# tophat-alumni.net
KiCad netlist of a schematic drawn in EAGLE
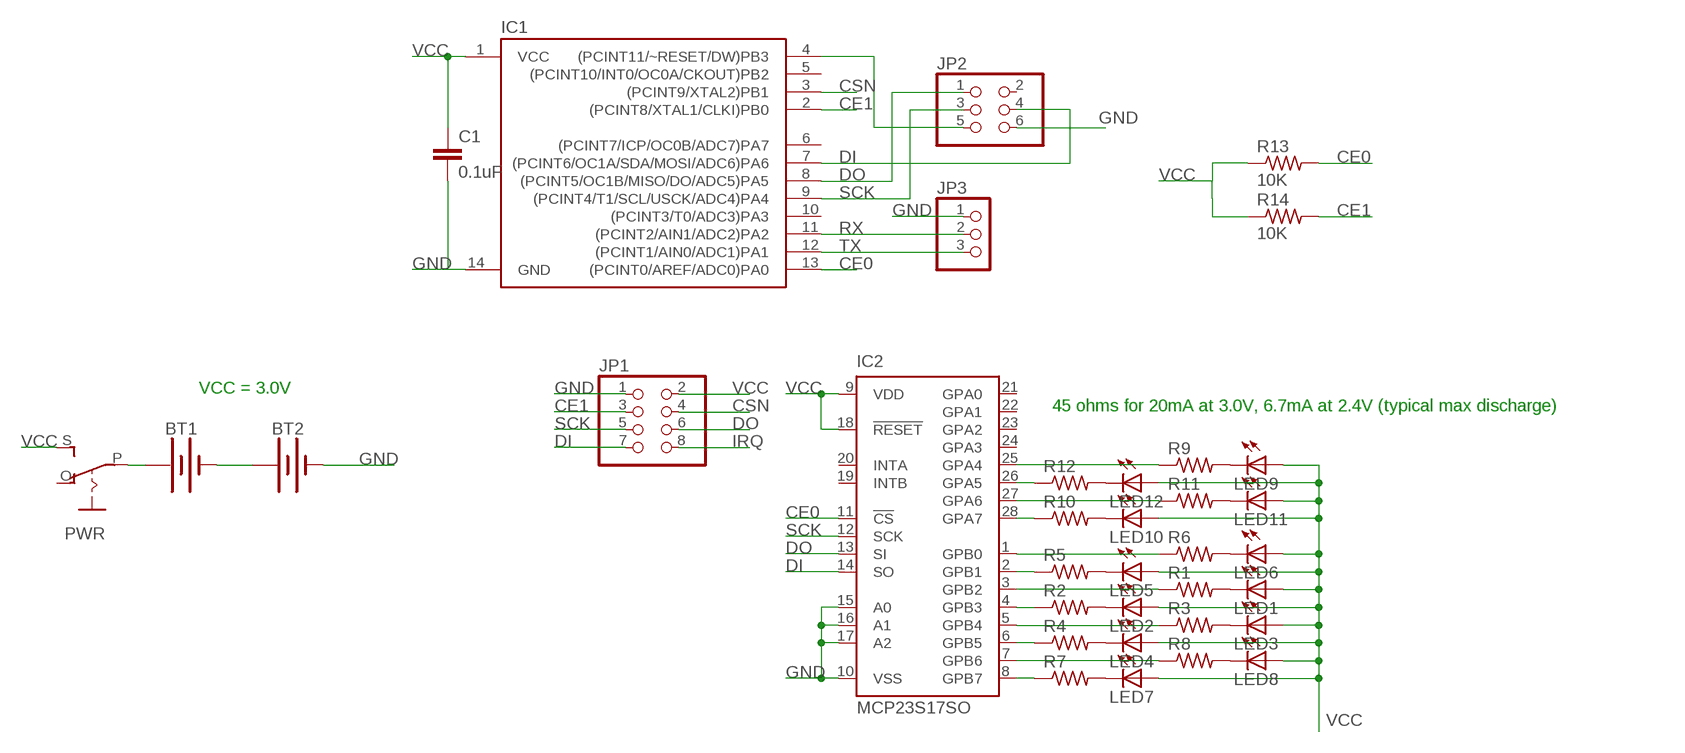
[diagram p0: schematic, sheet 1]

(export (version "E")
  (design (tool "Eeschema 10.0.6"))
  (components
    (comp (ref "BT1")
      (value "BATTERY-AA-SMD")
      (footprint "eagle-import:BATTERY-AA-SMD")
      (libsource (lib "eagle-import") (part "BATTERY-AA-SMD"))
    )
    (comp (ref "BT2")
      (value "BATTERY-AA-SMD")
      (footprint "eagle-import:BATTERY-AA-SMD")
      (libsource (lib "eagle-import") (part "BATTERY-AA-SMD"))
    )
    (comp (ref "C1")
      (value "0.1uF")
      (footprint "eagle-import:C1206")
      (libsource (lib "eagle-import") (part "C-EUC1206"))
    )
    (comp (ref "IC1")
      (value "ATTINY84")
      (footprint "eagle-import:SO14")
      (libsource (lib "eagle-import") (part "ATTINY84"))
    )
    (comp (ref "IC2")
      (value "MCP23S17SO")
      (footprint "eagle-import:SO28W")
      (fields (field (name "MF") "MICROCHIP") (field (name "MPN") "MCP23S17-E/SO"))
      (libsource (lib "eagle-import") (part "MCP23S17SO"))
    )
    (comp (ref "JP1")
      (value "PINHD-2X4/90")
      (footprint "eagle-import:2X04_90")
      (libsource (lib "eagle-import") (part "PINHD-2X4/90"))
    )
    (comp (ref "JP2")
      (value "PINHD-2X3")
      (footprint "eagle-import:2X03")
      (libsource (lib "eagle-import") (part "PINHD-2X3"))
    )
    (comp (ref "JP3")
      (value "PINHD-1X3")
      (footprint "eagle-import:1X03")
      (libsource (lib "eagle-import") (part "PINHD-1X3"))
    )
    (comp (ref "LED1")
      (value "LEDSMT1206")
      (footprint "eagle-import:1206")
      (libsource (lib "eagle-import") (part "LEDSMT1206"))
    )
    (comp (ref "LED2")
      (value "LEDSMT1206")
      (footprint "eagle-import:1206")
      (libsource (lib "eagle-import") (part "LEDSMT1206"))
    )
    (comp (ref "LED3")
      (value "LEDSMT1206")
      (footprint "eagle-import:1206")
      (libsource (lib "eagle-import") (part "LEDSMT1206"))
    )
    (comp (ref "LED4")
      (value "LEDSMT1206")
      (footprint "eagle-import:1206")
      (libsource (lib "eagle-import") (part "LEDSMT1206"))
    )
    (comp (ref "LED5")
      (value "LEDSMT1206")
      (footprint "eagle-import:1206")
      (libsource (lib "eagle-import") (part "LEDSMT1206"))
    )
    (comp (ref "LED6")
      (value "LEDSMT1206")
      (footprint "eagle-import:1206")
      (libsource (lib "eagle-import") (part "LEDSMT1206"))
    )
    (comp (ref "LED7")
      (value "LEDSMT1206")
      (footprint "eagle-import:1206")
      (libsource (lib "eagle-import") (part "LEDSMT1206"))
    )
    (comp (ref "LED8")
      (value "LEDSMT1206")
      (footprint "eagle-import:1206")
      (libsource (lib "eagle-import") (part "LEDSMT1206"))
    )
    (comp (ref "LED9")
      (value "LEDSMT1206")
      (footprint "eagle-import:1206")
      (libsource (lib "eagle-import") (part "LEDSMT1206"))
    )
    (comp (ref "LED10")
      (value "LEDSMT1206")
      (footprint "eagle-import:1206")
      (libsource (lib "eagle-import") (part "LEDSMT1206"))
    )
    (comp (ref "LED11")
      (value "LEDSMT1206")
      (footprint "eagle-import:1206")
      (libsource (lib "eagle-import") (part "LEDSMT1206"))
    )
    (comp (ref "LED12")
      (value "LEDSMT1206")
      (footprint "eagle-import:1206")
      (libsource (lib "eagle-import") (part "LEDSMT1206"))
    )
    (comp (ref "PWR")
      (value "EG1218S")
      (footprint "eagle-import:EG1218")
      (libsource (lib "eagle-import") (part "EG1218S"))
    )
    (comp (ref "R1")
      (value "R-US_R1206")
      (footprint "eagle-import:R1206")
      (libsource (lib "eagle-import") (part "R-US_R1206"))
    )
    (comp (ref "R2")
      (value "R-US_R1206")
      (footprint "eagle-import:R1206")
      (libsource (lib "eagle-import") (part "R-US_R1206"))
    )
    (comp (ref "R3")
      (value "R-US_R1206")
      (footprint "eagle-import:R1206")
      (libsource (lib "eagle-import") (part "R-US_R1206"))
    )
    (comp (ref "R4")
      (value "R-US_R1206")
      (footprint "eagle-import:R1206")
      (libsource (lib "eagle-import") (part "R-US_R1206"))
    )
    (comp (ref "R5")
      (value "R-US_R1206")
      (footprint "eagle-import:R1206")
      (libsource (lib "eagle-import") (part "R-US_R1206"))
    )
    (comp (ref "R6")
      (value "R-US_R1206")
      (footprint "eagle-import:R1206")
      (libsource (lib "eagle-import") (part "R-US_R1206"))
    )
    (comp (ref "R7")
      (value "R-US_R1206")
      (footprint "eagle-import:R1206")
      (libsource (lib "eagle-import") (part "R-US_R1206"))
    )
    (comp (ref "R8")
      (value "R-US_R1206")
      (footprint "eagle-import:R1206")
      (libsource (lib "eagle-import") (part "R-US_R1206"))
    )
    (comp (ref "R9")
      (value "R-US_R1206")
      (footprint "eagle-import:R1206")
      (libsource (lib "eagle-import") (part "R-US_R1206"))
    )
    (comp (ref "R10")
      (value "R-US_R1206")
      (footprint "eagle-import:R1206")
      (libsource (lib "eagle-import") (part "R-US_R1206"))
    )
    (comp (ref "R11")
      (value "R-US_R1206")
      (footprint "eagle-import:R1206")
      (libsource (lib "eagle-import") (part "R-US_R1206"))
    )
    (comp (ref "R12")
      (value "R-US_R1206")
      (footprint "eagle-import:R1206")
      (libsource (lib "eagle-import") (part "R-US_R1206"))
    )
    (comp (ref "R13")
      (value "10K")
      (footprint "eagle-import:R1206")
      (libsource (lib "eagle-import") (part "R-US_R1206"))
    )
    (comp (ref "R14")
      (value "10K")
      (footprint "eagle-import:R1206")
      (libsource (lib "eagle-import") (part "R-US_R1206"))
    )
  )
  (nets
    (net (code "1") (name "/CE0") (class "Default")
      (node (ref "IC1") (pin "13") (pinfunction "(PCINT0/AREF/ADC0)PA0_13") (pintype "bidirectional"))
      (node (ref "IC2") (pin "11") (pinfunction "~{CS}_11") (pintype "input"))
      (node (ref "R13") (pin "2") (pinfunction "2_2") (pintype "passive"))
    )
    (net (code "2") (name "/CE1") (class "Default")
      (node (ref "IC1") (pin "2") (pinfunction "(PCINT8/XTAL1/CLKI)PB0_2") (pintype "bidirectional"))
      (node (ref "JP1") (pin "3") (pinfunction "3_3") (pintype "passive"))
      (node (ref "R14") (pin "2") (pinfunction "2_2") (pintype "passive"))
    )
    (net (code "3") (name "/CSN") (class "Default")
      (node (ref "IC1") (pin "3") (pinfunction "(PCINT9/XTAL2)PB1_3") (pintype "bidirectional"))
      (node (ref "JP1") (pin "4") (pinfunction "4_4") (pintype "passive"))
    )
    (net (code "4") (name "/DI") (class "Default")
      (node (ref "IC1") (pin "7") (pinfunction "(PCINT6/OC1A/SDA/MOSI/ADC6)PA6_7") (pintype "bidirectional"))
      (node (ref "IC2") (pin "14") (pinfunction "SO_14") (pintype "output"))
      (node (ref "JP1") (pin "7") (pinfunction "7_7") (pintype "passive"))
      (node (ref "JP2") (pin "4") (pinfunction "4_4") (pintype "passive"))
    )
    (net (code "5") (name "/DO") (class "Default")
      (node (ref "IC1") (pin "8") (pinfunction "(PCINT5/OC1B/MISO/DO/ADC5)PA5_8") (pintype "bidirectional"))
      (node (ref "IC2") (pin "13") (pinfunction "SI_13") (pintype "input"))
      (node (ref "JP1") (pin "6") (pinfunction "6_6") (pintype "passive"))
      (node (ref "JP2") (pin "1") (pinfunction "1_1") (pintype "passive"))
    )
    (net (code "6") (name "/GND") (class "Default")
      (node (ref "BT2") (pin "P$2") (pinfunction "-_P$2") (pintype "power_in"))
      (node (ref "BT2") (pin "P$4") (pinfunction "-_P$4") (pintype "power_in"))
      (node (ref "C1") (pin "2") (pinfunction "2_2") (pintype "passive"))
      (node (ref "IC1") (pin "14") (pinfunction "GND_14") (pintype "bidirectional"))
      (node (ref "IC2") (pin "10") (pinfunction "VSS_10") (pintype "power_in"))
      (node (ref "IC2") (pin "15") (pinfunction "A0_15") (pintype "input"))
      (node (ref "IC2") (pin "16") (pinfunction "A1_16") (pintype "input"))
      (node (ref "IC2") (pin "17") (pinfunction "A2_17") (pintype "input"))
      (node (ref "JP1") (pin "1") (pinfunction "1_1") (pintype "passive"))
      (node (ref "JP2") (pin "6") (pinfunction "6_6") (pintype "passive"))
      (node (ref "JP3") (pin "1") (pinfunction "1_1") (pintype "passive"))
    )
    (net (code "7") (name "/IRQ") (class "Default")
      (node (ref "JP1") (pin "8") (pinfunction "8_8") (pintype "passive"))
    )
    (net (code "8") (name "/RX") (class "Default")
      (node (ref "IC1") (pin "11") (pinfunction "(PCINT2/AIN1/ADC2)PA2_11") (pintype "bidirectional"))
      (node (ref "JP3") (pin "2") (pinfunction "2_2") (pintype "passive"))
    )
    (net (code "9") (name "/SCK") (class "Default")
      (node (ref "IC1") (pin "9") (pinfunction "(PCINT4/T1/SCL/USCK/ADC4)PA4_9") (pintype "bidirectional"))
      (node (ref "IC2") (pin "12") (pinfunction "SCK_12") (pintype "input"))
      (node (ref "JP1") (pin "5") (pinfunction "5_5") (pintype "passive"))
      (node (ref "JP2") (pin "3") (pinfunction "3_3") (pintype "passive"))
    )
    (net (code "10") (name "/TX") (class "Default")
      (node (ref "IC1") (pin "12") (pinfunction "(PCINT1/AIN0/ADC1)PA1_12") (pintype "bidirectional"))
      (node (ref "JP3") (pin "3") (pinfunction "3_3") (pintype "passive"))
    )
    (net (code "11") (name "/VCC") (class "Default")
      (node (ref "C1") (pin "1") (pinfunction "1_1") (pintype "passive"))
      (node (ref "IC1") (pin "1") (pinfunction "VCC_1") (pintype "bidirectional"))
      (node (ref "IC2") (pin "18") (pinfunction "~{RESET}_18") (pintype "input"))
      (node (ref "IC2") (pin "9") (pinfunction "VDD_9") (pintype "power_in"))
      (node (ref "JP1") (pin "2") (pinfunction "2_2") (pintype "passive"))
      (node (ref "LED1") (pin "A") (pinfunction "A_A") (pintype "passive"))
      (node (ref "LED10") (pin "A") (pinfunction "A_A") (pintype "passive"))
      (node (ref "LED11") (pin "A") (pinfunction "A_A") (pintype "passive"))
      (node (ref "LED12") (pin "A") (pinfunction "A_A") (pintype "passive"))
      (node (ref "LED2") (pin "A") (pinfunction "A_A") (pintype "passive"))
      (node (ref "LED3") (pin "A") (pinfunction "A_A") (pintype "passive"))
      (node (ref "LED4") (pin "A") (pinfunction "A_A") (pintype "passive"))
      (node (ref "LED5") (pin "A") (pinfunction "A_A") (pintype "passive"))
      (node (ref "LED6") (pin "A") (pinfunction "A_A") (pintype "passive"))
      (node (ref "LED7") (pin "A") (pinfunction "A_A") (pintype "passive"))
      (node (ref "LED8") (pin "A") (pinfunction "A_A") (pintype "passive"))
      (node (ref "LED9") (pin "A") (pinfunction "A_A") (pintype "passive"))
      (node (ref "PWR") (pin "S") (pinfunction "S_S") (pintype "passive"))
      (node (ref "R13") (pin "1") (pinfunction "1_1") (pintype "passive"))
      (node (ref "R14") (pin "1") (pinfunction "1_1") (pintype "passive"))
    )
    (net (code "12") (name "Net-(BT1-+-PadP$1)") (class "Default")
      (node (ref "BT1") (pin "P$1") (pinfunction "+_P$1") (pintype "power_in"))
      (node (ref "BT1") (pin "P$3") (pinfunction "+_P$3") (pintype "power_in"))
      (node (ref "PWR") (pin "P") (pinfunction "P_P") (pintype "passive"))
    )
    (net (code "13") (name "Net-(BT1---PadP$2)") (class "Default")
      (node (ref "BT1") (pin "P$2") (pinfunction "-_P$2") (pintype "power_in"))
      (node (ref "BT1") (pin "P$4") (pinfunction "-_P$4") (pintype "power_in"))
      (node (ref "BT2") (pin "P$1") (pinfunction "+_P$1") (pintype "power_in"))
      (node (ref "BT2") (pin "P$3") (pinfunction "+_P$3") (pintype "power_in"))
    )
    (net (code "14") (name "Net-(IC1-(PCINT11{slash}~{RESET{slash}DW})PB3)") (class "Default")
      (node (ref "IC1") (pin "4") (pinfunction "(PCINT11/~{RESET/DW})PB3_4") (pintype "bidirectional"))
      (node (ref "JP2") (pin "5") (pinfunction "5_5") (pintype "passive"))
    )
    (net (code "15") (name "Net-(IC2-GPA4)") (class "Default")
      (node (ref "IC2") (pin "25") (pinfunction "GPA4_25") (pintype "bidirectional"))
      (node (ref "R9") (pin "1") (pinfunction "1_1") (pintype "passive"))
    )
    (net (code "16") (name "Net-(IC2-GPA5)") (class "Default")
      (node (ref "IC2") (pin "26") (pinfunction "GPA5_26") (pintype "bidirectional"))
      (node (ref "R12") (pin "1") (pinfunction "1_1") (pintype "passive"))
    )
    (net (code "17") (name "Net-(IC2-GPA6)") (class "Default")
      (node (ref "IC2") (pin "27") (pinfunction "GPA6_27") (pintype "bidirectional"))
      (node (ref "R11") (pin "1") (pinfunction "1_1") (pintype "passive"))
    )
    (net (code "18") (name "Net-(IC2-GPA7)") (class "Default")
      (node (ref "IC2") (pin "28") (pinfunction "GPA7_28") (pintype "bidirectional"))
      (node (ref "R10") (pin "1") (pinfunction "1_1") (pintype "passive"))
    )
    (net (code "19") (name "Net-(IC2-GPB0)") (class "Default")
      (node (ref "IC2") (pin "1") (pinfunction "GPB0_1") (pintype "bidirectional"))
      (node (ref "R6") (pin "1") (pinfunction "1_1") (pintype "passive"))
    )
    (net (code "20") (name "Net-(IC2-GPB1)") (class "Default")
      (node (ref "IC2") (pin "2") (pinfunction "GPB1_2") (pintype "bidirectional"))
      (node (ref "R5") (pin "1") (pinfunction "1_1") (pintype "passive"))
    )
    (net (code "21") (name "Net-(IC2-GPB2)") (class "Default")
      (node (ref "IC2") (pin "3") (pinfunction "GPB2_3") (pintype "bidirectional"))
      (node (ref "R1") (pin "1") (pinfunction "1_1") (pintype "passive"))
    )
    (net (code "22") (name "Net-(IC2-GPB3)") (class "Default")
      (node (ref "IC2") (pin "4") (pinfunction "GPB3_4") (pintype "bidirectional"))
      (node (ref "R2") (pin "1") (pinfunction "1_1") (pintype "passive"))
    )
    (net (code "23") (name "Net-(IC2-GPB4)") (class "Default")
      (node (ref "IC2") (pin "5") (pinfunction "GPB4_5") (pintype "bidirectional"))
      (node (ref "R3") (pin "1") (pinfunction "1_1") (pintype "passive"))
    )
    (net (code "24") (name "Net-(IC2-GPB5)") (class "Default")
      (node (ref "IC2") (pin "6") (pinfunction "GPB5_6") (pintype "bidirectional"))
      (node (ref "R4") (pin "1") (pinfunction "1_1") (pintype "passive"))
    )
    (net (code "25") (name "Net-(IC2-GPB6)") (class "Default")
      (node (ref "IC2") (pin "7") (pinfunction "GPB6_7") (pintype "bidirectional"))
      (node (ref "R8") (pin "1") (pinfunction "1_1") (pintype "passive"))
    )
    (net (code "26") (name "Net-(IC2-GPB7)") (class "Default")
      (node (ref "IC2") (pin "8") (pinfunction "GPB7_8") (pintype "bidirectional"))
      (node (ref "R7") (pin "1") (pinfunction "1_1") (pintype "passive"))
    )
    (net (code "27") (name "Net-(LED1-PadC)") (class "Default")
      (node (ref "LED1") (pin "C") (pinfunction "C_C") (pintype "passive"))
      (node (ref "R1") (pin "2") (pinfunction "2_2") (pintype "passive"))
    )
    (net (code "28") (name "Net-(LED2-PadC)") (class "Default")
      (node (ref "LED2") (pin "C") (pinfunction "C_C") (pintype "passive"))
      (node (ref "R2") (pin "2") (pinfunction "2_2") (pintype "passive"))
    )
    (net (code "29") (name "Net-(LED3-PadC)") (class "Default")
      (node (ref "LED3") (pin "C") (pinfunction "C_C") (pintype "passive"))
      (node (ref "R3") (pin "2") (pinfunction "2_2") (pintype "passive"))
    )
    (net (code "30") (name "Net-(LED4-PadC)") (class "Default")
      (node (ref "LED4") (pin "C") (pinfunction "C_C") (pintype "passive"))
      (node (ref "R4") (pin "2") (pinfunction "2_2") (pintype "passive"))
    )
    (net (code "31") (name "Net-(LED5-PadC)") (class "Default")
      (node (ref "LED5") (pin "C") (pinfunction "C_C") (pintype "passive"))
      (node (ref "R5") (pin "2") (pinfunction "2_2") (pintype "passive"))
    )
    (net (code "32") (name "Net-(LED6-PadC)") (class "Default")
      (node (ref "LED6") (pin "C") (pinfunction "C_C") (pintype "passive"))
      (node (ref "R6") (pin "2") (pinfunction "2_2") (pintype "passive"))
    )
    (net (code "33") (name "Net-(LED7-PadC)") (class "Default")
      (node (ref "LED7") (pin "C") (pinfunction "C_C") (pintype "passive"))
      (node (ref "R7") (pin "2") (pinfunction "2_2") (pintype "passive"))
    )
    (net (code "34") (name "Net-(LED8-PadC)") (class "Default")
      (node (ref "LED8") (pin "C") (pinfunction "C_C") (pintype "passive"))
      (node (ref "R8") (pin "2") (pinfunction "2_2") (pintype "passive"))
    )
    (net (code "35") (name "Net-(LED9-PadC)") (class "Default")
      (node (ref "LED9") (pin "C") (pinfunction "C_C") (pintype "passive"))
      (node (ref "R9") (pin "2") (pinfunction "2_2") (pintype "passive"))
    )
    (net (code "36") (name "Net-(LED10-PadC)") (class "Default")
      (node (ref "LED10") (pin "C") (pinfunction "C_C") (pintype "passive"))
      (node (ref "R10") (pin "2") (pinfunction "2_2") (pintype "passive"))
    )
    (net (code "37") (name "Net-(LED11-PadC)") (class "Default")
      (node (ref "LED11") (pin "C") (pinfunction "C_C") (pintype "passive"))
      (node (ref "R11") (pin "2") (pinfunction "2_2") (pintype "passive"))
    )
    (net (code "38") (name "Net-(LED12-PadC)") (class "Default")
      (node (ref "LED12") (pin "C") (pinfunction "C_C") (pintype "passive"))
      (node (ref "R12") (pin "2") (pinfunction "2_2") (pintype "passive"))
    )
    (net (code "39") (name "unconnected-(IC1-(PCINT3{slash}T0{slash}ADC3)PA3-Pad10)") (class "Default")
      (node (ref "IC1") (pin "10") (pinfunction "(PCINT3/T0/ADC3)PA3_10") (pintype "bidirectional"))
    )
    (net (code "40") (name "unconnected-(IC1-(PCINT7{slash}ICP{slash}OC0B{slash}ADC7)PA7-Pad6)") (class "Default")
      (node (ref "IC1") (pin "6") (pinfunction "(PCINT7/ICP/OC0B/ADC7)PA7_6") (pintype "bidirectional"))
    )
    (net (code "41") (name "unconnected-(IC1-(PCINT10{slash}INT0{slash}OC0A{slash}CKOUT)PB2-Pad5)") (class "Default")
      (node (ref "IC1") (pin "5") (pinfunction "(PCINT10/INT0/OC0A/CKOUT)PB2_5") (pintype "bidirectional"))
    )
    (net (code "42") (name "unconnected-(IC2-GPA0-Pad21)") (class "Default")
      (node (ref "IC2") (pin "21") (pinfunction "GPA0_21") (pintype "bidirectional"))
    )
    (net (code "43") (name "unconnected-(IC2-GPA1-Pad22)") (class "Default")
      (node (ref "IC2") (pin "22") (pinfunction "GPA1_22") (pintype "bidirectional"))
    )
    (net (code "44") (name "unconnected-(IC2-GPA2-Pad23)") (class "Default")
      (node (ref "IC2") (pin "23") (pinfunction "GPA2_23") (pintype "bidirectional"))
    )
    (net (code "45") (name "unconnected-(IC2-GPA3-Pad24)") (class "Default")
      (node (ref "IC2") (pin "24") (pinfunction "GPA3_24") (pintype "bidirectional"))
    )
    (net (code "46") (name "unconnected-(IC2-INTA-Pad20)") (class "Default")
      (node (ref "IC2") (pin "20") (pinfunction "INTA_20") (pintype "output"))
    )
    (net (code "47") (name "unconnected-(IC2-INTB-Pad19)") (class "Default")
      (node (ref "IC2") (pin "19") (pinfunction "INTB_19") (pintype "output"))
    )
    (net (code "48") (name "unconnected-(JP2-Pad2)") (class "Default")
      (node (ref "JP2") (pin "2") (pinfunction "2_2") (pintype "passive"))
    )
    (net (code "49") (name "unconnected-(PWR-PadO)") (class "Default")
      (node (ref "PWR") (pin "O") (pinfunction "O_O") (pintype "passive"))
    )
  )
)
